# Sheet1.net
KiCad netlist of a schematic drawn in Altium Designer
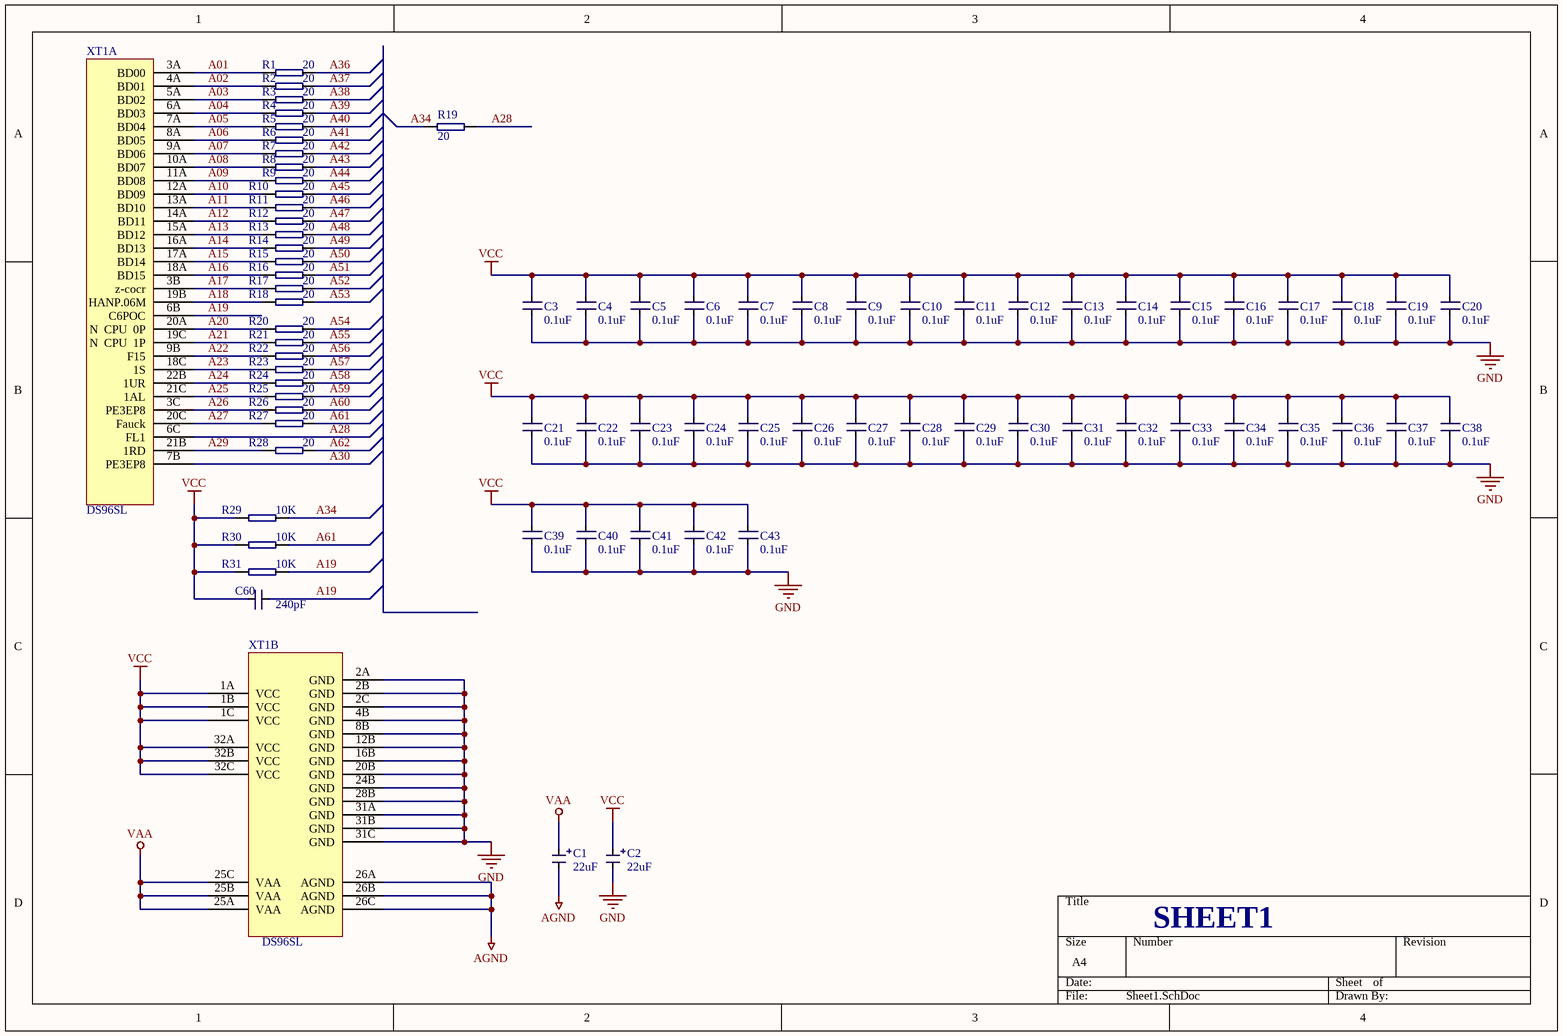
[diagram p0: Sheet1.SchDoc]

(export (version "E")
  (design (tool "Eeschema 10.0.6"))
  (components
    (comp (ref "C1")
      (value "22uF")
      (footprint "B(1812)")
      (fields (field (name "Comment") "Cap2"))
      (libsource (lib "Board2") (part "Cap2"))
    )
    (comp (ref "C2")
      (value "22uF")
      (footprint "B(1812)")
      (fields (field (name "Comment") "Cap2"))
      (libsource (lib "Board2") (part "Cap2"))
    )
    (comp (ref "C3")
      (value "0.1uF")
      (footprint "0805")
      (fields (field (name "Comment") "Cap"))
      (libsource (lib "Board2") (part "Cap"))
    )
    (comp (ref "C4")
      (value "0.1uF")
      (footprint "0805")
      (fields (field (name "Comment") "Cap"))
      (libsource (lib "Board2") (part "Cap"))
    )
    (comp (ref "C5")
      (value "0.1uF")
      (footprint "0805")
      (fields (field (name "Comment") "Cap"))
      (libsource (lib "Board2") (part "Cap"))
    )
    (comp (ref "C6")
      (value "0.1uF")
      (footprint "0805")
      (fields (field (name "Comment") "Cap"))
      (libsource (lib "Board2") (part "Cap"))
    )
    (comp (ref "C7")
      (value "0.1uF")
      (footprint "0805")
      (fields (field (name "Comment") "Cap"))
      (libsource (lib "Board2") (part "Cap"))
    )
    (comp (ref "C8")
      (value "0.1uF")
      (footprint "0805")
      (fields (field (name "Comment") "Cap"))
      (libsource (lib "Board2") (part "Cap"))
    )
    (comp (ref "C9")
      (value "0.1uF")
      (footprint "0805")
      (fields (field (name "Comment") "Cap"))
      (libsource (lib "Board2") (part "Cap"))
    )
    (comp (ref "C10")
      (value "0.1uF")
      (footprint "0805")
      (fields (field (name "Comment") "Cap"))
      (libsource (lib "Board2") (part "Cap"))
    )
    (comp (ref "C11")
      (value "0.1uF")
      (footprint "0805")
      (fields (field (name "Comment") "Cap"))
      (libsource (lib "Board2") (part "Cap"))
    )
    (comp (ref "C12")
      (value "0.1uF")
      (footprint "0805")
      (fields (field (name "Comment") "Cap"))
      (libsource (lib "Board2") (part "Cap"))
    )
    (comp (ref "C13")
      (value "0.1uF")
      (footprint "0805")
      (fields (field (name "Comment") "Cap"))
      (libsource (lib "Board2") (part "Cap"))
    )
    (comp (ref "C14")
      (value "0.1uF")
      (footprint "0805")
      (fields (field (name "Comment") "Cap"))
      (libsource (lib "Board2") (part "Cap"))
    )
    (comp (ref "C15")
      (value "0.1uF")
      (footprint "0805")
      (fields (field (name "Comment") "Cap"))
      (libsource (lib "Board2") (part "Cap"))
    )
    (comp (ref "C16")
      (value "0.1uF")
      (footprint "0805")
      (fields (field (name "Comment") "Cap"))
      (libsource (lib "Board2") (part "Cap"))
    )
    (comp (ref "C17")
      (value "0.1uF")
      (footprint "0805")
      (fields (field (name "Comment") "Cap"))
      (libsource (lib "Board2") (part "Cap"))
    )
    (comp (ref "C18")
      (value "0.1uF")
      (footprint "0805")
      (fields (field (name "Comment") "Cap"))
      (libsource (lib "Board2") (part "Cap"))
    )
    (comp (ref "C19")
      (value "0.1uF")
      (footprint "0805")
      (fields (field (name "Comment") "Cap"))
      (libsource (lib "Board2") (part "Cap"))
    )
    (comp (ref "C20")
      (value "0.1uF")
      (footprint "0805")
      (fields (field (name "Comment") "Cap"))
      (libsource (lib "Board2") (part "Cap"))
    )
    (comp (ref "C21")
      (value "0.1uF")
      (footprint "0805")
      (fields (field (name "Comment") "Cap"))
      (libsource (lib "Board2") (part "Cap"))
    )
    (comp (ref "C22")
      (value "0.1uF")
      (footprint "0805")
      (fields (field (name "Comment") "Cap"))
      (libsource (lib "Board2") (part "Cap"))
    )
    (comp (ref "C23")
      (value "0.1uF")
      (footprint "0805")
      (fields (field (name "Comment") "Cap"))
      (libsource (lib "Board2") (part "Cap"))
    )
    (comp (ref "C24")
      (value "0.1uF")
      (footprint "0805")
      (fields (field (name "Comment") "Cap"))
      (libsource (lib "Board2") (part "Cap"))
    )
    (comp (ref "C25")
      (value "0.1uF")
      (footprint "0805")
      (fields (field (name "Comment") "Cap"))
      (libsource (lib "Board2") (part "Cap"))
    )
    (comp (ref "C26")
      (value "0.1uF")
      (footprint "0805")
      (fields (field (name "Comment") "Cap"))
      (libsource (lib "Board2") (part "Cap"))
    )
    (comp (ref "C27")
      (value "0.1uF")
      (footprint "0805")
      (fields (field (name "Comment") "Cap"))
      (libsource (lib "Board2") (part "Cap"))
    )
    (comp (ref "C28")
      (value "0.1uF")
      (footprint "0805")
      (fields (field (name "Comment") "Cap"))
      (libsource (lib "Board2") (part "Cap"))
    )
    (comp (ref "C29")
      (value "0.1uF")
      (footprint "0805")
      (fields (field (name "Comment") "Cap"))
      (libsource (lib "Board2") (part "Cap"))
    )
    (comp (ref "C30")
      (value "0.1uF")
      (footprint "0805")
      (fields (field (name "Comment") "Cap"))
      (libsource (lib "Board2") (part "Cap"))
    )
    (comp (ref "C31")
      (value "0.1uF")
      (footprint "0805")
      (fields (field (name "Comment") "Cap"))
      (libsource (lib "Board2") (part "Cap"))
    )
    (comp (ref "C32")
      (value "0.1uF")
      (footprint "0805")
      (fields (field (name "Comment") "Cap"))
      (libsource (lib "Board2") (part "Cap"))
    )
    (comp (ref "C33")
      (value "0.1uF")
      (footprint "0805")
      (fields (field (name "Comment") "Cap"))
      (libsource (lib "Board2") (part "Cap"))
    )
    (comp (ref "C34")
      (value "0.1uF")
      (footprint "0805")
      (fields (field (name "Comment") "Cap"))
      (libsource (lib "Board2") (part "Cap"))
    )
    (comp (ref "C35")
      (value "0.1uF")
      (footprint "0805")
      (fields (field (name "Comment") "Cap"))
      (libsource (lib "Board2") (part "Cap"))
    )
    (comp (ref "C36")
      (value "0.1uF")
      (footprint "0805")
      (fields (field (name "Comment") "Cap"))
      (libsource (lib "Board2") (part "Cap"))
    )
    (comp (ref "C37")
      (value "0.1uF")
      (footprint "0805")
      (fields (field (name "Comment") "Cap"))
      (libsource (lib "Board2") (part "Cap"))
    )
    (comp (ref "C38")
      (value "0.1uF")
      (footprint "0805")
      (fields (field (name "Comment") "Cap"))
      (libsource (lib "Board2") (part "Cap"))
    )
    (comp (ref "C39")
      (value "0.1uF")
      (footprint "0805")
      (fields (field (name "Comment") "Cap"))
      (libsource (lib "Board2") (part "Cap"))
    )
    (comp (ref "C40")
      (value "0.1uF")
      (footprint "0805")
      (fields (field (name "Comment") "Cap"))
      (libsource (lib "Board2") (part "Cap"))
    )
    (comp (ref "C41")
      (value "0.1uF")
      (footprint "0805")
      (fields (field (name "Comment") "Cap"))
      (libsource (lib "Board2") (part "Cap"))
    )
    (comp (ref "C42")
      (value "0.1uF")
      (footprint "0805")
      (fields (field (name "Comment") "Cap"))
      (libsource (lib "Board2") (part "Cap"))
    )
    (comp (ref "C43")
      (value "0.1uF")
      (footprint "0805")
      (fields (field (name "Comment") "Cap"))
      (libsource (lib "Board2") (part "Cap"))
    )
    (comp (ref "C60")
      (value "240pF")
      (footprint "0805")
      (fields (field (name "Comment") "Cap"))
      (libsource (lib "Board2") (part "Cap"))
    )
    (comp (ref "R1")
      (value "20")
      (footprint "0805")
      (fields (field (name "Comment") "R"))
      (libsource (lib "Board2") (part "R"))
    )
    (comp (ref "R2")
      (value "20")
      (footprint "0805")
      (fields (field (name "Comment") "R"))
      (libsource (lib "Board2") (part "R"))
    )
    (comp (ref "R3")
      (value "20")
      (footprint "0805")
      (fields (field (name "Comment") "R"))
      (libsource (lib "Board2") (part "R"))
    )
    (comp (ref "R4")
      (value "20")
      (footprint "0805")
      (fields (field (name "Comment") "R"))
      (libsource (lib "Board2") (part "R"))
    )
    (comp (ref "R5")
      (value "20")
      (footprint "0805")
      (fields (field (name "Comment") "R"))
      (libsource (lib "Board2") (part "R"))
    )
    (comp (ref "R6")
      (value "20")
      (footprint "0805")
      (fields (field (name "Comment") "R"))
      (libsource (lib "Board2") (part "R"))
    )
    (comp (ref "R7")
      (value "20")
      (footprint "0805")
      (fields (field (name "Comment") "R"))
      (libsource (lib "Board2") (part "R"))
    )
    (comp (ref "R8")
      (value "20")
      (footprint "0805")
      (fields (field (name "Comment") "R"))
      (libsource (lib "Board2") (part "R"))
    )
    (comp (ref "R9")
      (value "20")
      (footprint "0805")
      (fields (field (name "Comment") "R"))
      (libsource (lib "Board2") (part "R"))
    )
    (comp (ref "R10")
      (value "20")
      (footprint "0805")
      (fields (field (name "Comment") "R"))
      (libsource (lib "Board2") (part "R"))
    )
    (comp (ref "R11")
      (value "20")
      (footprint "0805")
      (fields (field (name "Comment") "R"))
      (libsource (lib "Board2") (part "R"))
    )
    (comp (ref "R12")
      (value "20")
      (footprint "0805")
      (fields (field (name "Comment") "R"))
      (libsource (lib "Board2") (part "R"))
    )
    (comp (ref "R13")
      (value "20")
      (footprint "0805")
      (fields (field (name "Comment") "R"))
      (libsource (lib "Board2") (part "R"))
    )
    (comp (ref "R14")
      (value "20")
      (footprint "0805")
      (fields (field (name "Comment") "R"))
      (libsource (lib "Board2") (part "R"))
    )
    (comp (ref "R15")
      (value "20")
      (footprint "0805")
      (fields (field (name "Comment") "R"))
      (libsource (lib "Board2") (part "R"))
    )
    (comp (ref "R16")
      (value "20")
      (footprint "0805")
      (fields (field (name "Comment") "R"))
      (libsource (lib "Board2") (part "R"))
    )
    (comp (ref "R17")
      (value "20")
      (footprint "0805")
      (fields (field (name "Comment") "R"))
      (libsource (lib "Board2") (part "R"))
    )
    (comp (ref "R18")
      (value "20")
      (footprint "0805")
      (fields (field (name "Comment") "R"))
      (libsource (lib "Board2") (part "R"))
    )
    (comp (ref "R19")
      (value "20")
      (footprint "0805")
      (fields (field (name "Comment") "R"))
      (libsource (lib "") (part "R_1"))
    )
    (comp (ref "R20")
      (value "20")
      (footprint "0805")
      (fields (field (name "Comment") "R"))
      (libsource (lib "Board2") (part "R"))
    )
    (comp (ref "R21")
      (value "20")
      (footprint "0805")
      (fields (field (name "Comment") "R"))
      (libsource (lib "Board2") (part "R"))
    )
    (comp (ref "R22")
      (value "20")
      (footprint "0805")
      (fields (field (name "Comment") "R"))
      (libsource (lib "Board2") (part "R"))
    )
    (comp (ref "R23")
      (value "20")
      (footprint "0805")
      (fields (field (name "Comment") "R"))
      (libsource (lib "Board2") (part "R"))
    )
    (comp (ref "R24")
      (value "20")
      (footprint "0805")
      (fields (field (name "Comment") "R"))
      (libsource (lib "Board2") (part "R"))
    )
    (comp (ref "R25")
      (value "20")
      (footprint "0805")
      (fields (field (name "Comment") "R"))
      (libsource (lib "Board2") (part "R"))
    )
    (comp (ref "R26")
      (value "20")
      (footprint "0805")
      (fields (field (name "Comment") "R"))
      (libsource (lib "Board2") (part "R"))
    )
    (comp (ref "R27")
      (value "20")
      (footprint "0805")
      (fields (field (name "Comment") "R"))
      (libsource (lib "Board2") (part "R"))
    )
    (comp (ref "R28")
      (value "20")
      (footprint "0805")
      (fields (field (name "Comment") "R"))
      (libsource (lib "Board2") (part "R"))
    )
    (comp (ref "R29")
      (value "10K")
      (footprint "0805")
      (fields (field (name "Comment") "R"))
      (libsource (lib "Board2") (part "R"))
    )
    (comp (ref "R30")
      (value "10K")
      (footprint "0805")
      (fields (field (name "Comment") "R"))
      (libsource (lib "Board2") (part "R"))
    )
    (comp (ref "R31")
      (value "10K")
      (footprint "0805")
      (fields (field (name "Comment") "R"))
      (libsource (lib "Board2") (part "R"))
    )
    (comp (ref "XT1") (value "DS96SL") (footprint "DS96") (libsource (lib "Board2") (part "DS96SL")))
  )
  (nets
    (net (code "1") (name "/A01") (class "Default")
      (node (ref "R1") (pin "1") (pinfunction "1_1") (pintype "passive"))
      (node (ref "XT1") (pin "3A") (pinfunction "BD00_3A") (pintype "passive"))
    )
    (net (code "2") (name "/A02") (class "Default")
      (node (ref "R2") (pin "1") (pinfunction "1_1") (pintype "passive"))
      (node (ref "XT1") (pin "4A") (pinfunction "BD01_4A") (pintype "passive"))
    )
    (net (code "3") (name "/A03") (class "Default")
      (node (ref "R3") (pin "1") (pinfunction "1_1") (pintype "passive"))
      (node (ref "XT1") (pin "5A") (pinfunction "BD02_5A") (pintype "passive"))
    )
    (net (code "4") (name "/A04") (class "Default")
      (node (ref "R4") (pin "1") (pinfunction "1_1") (pintype "passive"))
      (node (ref "XT1") (pin "6A") (pinfunction "BD03_6A") (pintype "passive"))
    )
    (net (code "5") (name "/A05") (class "Default")
      (node (ref "R5") (pin "1") (pinfunction "1_1") (pintype "passive"))
      (node (ref "XT1") (pin "7A") (pinfunction "BD04_7A") (pintype "passive"))
    )
    (net (code "6") (name "/A06") (class "Default")
      (node (ref "R6") (pin "1") (pinfunction "1_1") (pintype "passive"))
      (node (ref "XT1") (pin "8A") (pinfunction "BD05_8A") (pintype "passive"))
    )
    (net (code "7") (name "/A07") (class "Default")
      (node (ref "R7") (pin "1") (pinfunction "1_1") (pintype "passive"))
      (node (ref "XT1") (pin "9A") (pinfunction "BD06_9A") (pintype "passive"))
    )
    (net (code "8") (name "/A08") (class "Default")
      (node (ref "R8") (pin "1") (pinfunction "1_1") (pintype "passive"))
      (node (ref "XT1") (pin "10A") (pinfunction "BD07_10A") (pintype "passive"))
    )
    (net (code "9") (name "/A09") (class "Default")
      (node (ref "R9") (pin "1") (pinfunction "1_1") (pintype "passive"))
      (node (ref "XT1") (pin "11A") (pinfunction "BD08_11A") (pintype "passive"))
    )
    (net (code "10") (name "/A10") (class "Default")
      (node (ref "R10") (pin "1") (pinfunction "1_1") (pintype "passive"))
      (node (ref "XT1") (pin "12A") (pinfunction "BD09_12A") (pintype "passive"))
    )
    (net (code "11") (name "/A11") (class "Default")
      (node (ref "R11") (pin "1") (pinfunction "1_1") (pintype "passive"))
      (node (ref "XT1") (pin "13A") (pinfunction "BD10_13A") (pintype "passive"))
    )
    (net (code "12") (name "/A12") (class "Default")
      (node (ref "R12") (pin "1") (pinfunction "1_1") (pintype "passive"))
      (node (ref "XT1") (pin "14A") (pinfunction "BD11_14A") (pintype "passive"))
    )
    (net (code "13") (name "/A13") (class "Default")
      (node (ref "R13") (pin "1") (pinfunction "1_1") (pintype "passive"))
      (node (ref "XT1") (pin "15A") (pinfunction "BD12_15A") (pintype "passive"))
    )
    (net (code "14") (name "/A14") (class "Default")
      (node (ref "R14") (pin "1") (pinfunction "1_1") (pintype "passive"))
      (node (ref "XT1") (pin "16A") (pinfunction "BD13_16A") (pintype "passive"))
    )
    (net (code "15") (name "/A15") (class "Default")
      (node (ref "R15") (pin "1") (pinfunction "1_1") (pintype "passive"))
      (node (ref "XT1") (pin "17A") (pinfunction "BD14_17A") (pintype "passive"))
    )
    (net (code "16") (name "/A16") (class "Default")
      (node (ref "R16") (pin "1") (pinfunction "1_1") (pintype "passive"))
      (node (ref "XT1") (pin "18A") (pinfunction "BD15_18A") (pintype "passive"))
    )
    (net (code "17") (name "/A17") (class "Default")
      (node (ref "R17") (pin "1") (pinfunction "1_1") (pintype "passive"))
      (node (ref "XT1") (pin "3B") (pinfunction "z-cocr_3B") (pintype "passive"))
    )
    (net (code "18") (name "/A18") (class "Default")
      (node (ref "R18") (pin "1") (pinfunction "1_1") (pintype "passive"))
      (node (ref "XT1") (pin "19B") (pinfunction "HANP.06M_19B") (pintype "passive"))
    )
    (net (code "19") (name "/A19") (class "Default")
      (node (ref "C60") (pin "2") (pinfunction "0_2") (pintype "passive"))
      (node (ref "R31") (pin "2") (pinfunction "0_2") (pintype "passive"))
      (node (ref "XT1") (pin "6B") (pinfunction "C6POC_6B") (pintype "passive"))
    )
    (net (code "20") (name "/A20") (class "Default")
      (node (ref "R20") (pin "1") (pinfunction "1_1") (pintype "passive"))
      (node (ref "XT1") (pin "20A") (pinfunction "N__CPU__0P_20A") (pintype "passive"))
    )
    (net (code "21") (name "/A21") (class "Default")
      (node (ref "R21") (pin "1") (pinfunction "1_1") (pintype "passive"))
      (node (ref "XT1") (pin "19C") (pinfunction "N__CPU__1P_19C") (pintype "passive"))
    )
    (net (code "22") (name "/A22") (class "Default")
      (node (ref "R22") (pin "1") (pinfunction "1_1") (pintype "passive"))
      (node (ref "XT1") (pin "9B") (pinfunction "F15_9B") (pintype "passive"))
    )
    (net (code "23") (name "/A23") (class "Default")
      (node (ref "R23") (pin "1") (pinfunction "1_1") (pintype "passive"))
      (node (ref "XT1") (pin "18C") (pinfunction "1S_18C") (pintype "passive"))
    )
    (net (code "24") (name "/A24") (class "Default")
      (node (ref "R24") (pin "1") (pinfunction "1_1") (pintype "passive"))
      (node (ref "XT1") (pin "22B") (pinfunction "1UR_22B") (pintype "passive"))
    )
    (net (code "25") (name "/A25") (class "Default")
      (node (ref "R25") (pin "1") (pinfunction "1_1") (pintype "passive"))
      (node (ref "XT1") (pin "21C") (pinfunction "1AL_21C") (pintype "passive"))
    )
    (net (code "26") (name "/A26") (class "Default")
      (node (ref "R26") (pin "1") (pinfunction "1_1") (pintype "passive"))
      (node (ref "XT1") (pin "3C") (pinfunction "PE3EP8_3C") (pintype "passive"))
    )
    (net (code "27") (name "/A27") (class "Default")
      (node (ref "R27") (pin "1") (pinfunction "1_1") (pintype "passive"))
      (node (ref "XT1") (pin "20C") (pinfunction "Fauck_20C") (pintype "passive"))
    )
    (net (code "28") (name "/A28") (class "Default")
      (node (ref "R19") (pin "1") (pinfunction "1_1") (pintype "passive"))
      (node (ref "XT1") (pin "6C") (pinfunction "FL1_6C") (pintype "passive"))
    )
    (net (code "29") (name "/A29") (class "Default")
      (node (ref "R28") (pin "1") (pinfunction "1_1") (pintype "passive"))
      (node (ref "XT1") (pin "21B") (pinfunction "1RD_21B") (pintype "passive"))
    )
    (net (code "30") (name "/A30") (class "Default")
      (node (ref "XT1") (pin "7B") (pinfunction "PE3EP8_7B") (pintype "passive"))
    )
    (net (code "31") (name "/A34") (class "Default")
      (node (ref "R19") (pin "2") (pinfunction "0_2") (pintype "passive"))
      (node (ref "R29") (pin "2") (pinfunction "0_2") (pintype "passive"))
    )
    (net (code "32") (name "/A36") (class "Default")
      (node (ref "R1") (pin "2") (pinfunction "0_2") (pintype "passive"))
    )
    (net (code "33") (name "/A37") (class "Default")
      (node (ref "R2") (pin "2") (pinfunction "0_2") (pintype "passive"))
    )
    (net (code "34") (name "/A38") (class "Default")
      (node (ref "R3") (pin "2") (pinfunction "0_2") (pintype "passive"))
    )
    (net (code "35") (name "/A39") (class "Default")
      (node (ref "R4") (pin "2") (pinfunction "0_2") (pintype "passive"))
    )
    (net (code "36") (name "/A40") (class "Default")
      (node (ref "R5") (pin "2") (pinfunction "0_2") (pintype "passive"))
    )
    (net (code "37") (name "/A41") (class "Default")
      (node (ref "R6") (pin "2") (pinfunction "0_2") (pintype "passive"))
    )
    (net (code "38") (name "/A42") (class "Default")
      (node (ref "R7") (pin "2") (pinfunction "0_2") (pintype "passive"))
    )
    (net (code "39") (name "/A43") (class "Default")
      (node (ref "R8") (pin "2") (pinfunction "0_2") (pintype "passive"))
    )
    (net (code "40") (name "/A44") (class "Default")
      (node (ref "R9") (pin "2") (pinfunction "0_2") (pintype "passive"))
    )
    (net (code "41") (name "/A45") (class "Default")
      (node (ref "R10") (pin "2") (pinfunction "0_2") (pintype "passive"))
    )
    (net (code "42") (name "/A46") (class "Default")
      (node (ref "R11") (pin "2") (pinfunction "0_2") (pintype "passive"))
    )
    (net (code "43") (name "/A47") (class "Default")
      (node (ref "R12") (pin "2") (pinfunction "0_2") (pintype "passive"))
    )
    (net (code "44") (name "/A48") (class "Default")
      (node (ref "R13") (pin "2") (pinfunction "0_2") (pintype "passive"))
    )
    (net (code "45") (name "/A49") (class "Default")
      (node (ref "R14") (pin "2") (pinfunction "0_2") (pintype "passive"))
    )
    (net (code "46") (name "/A50") (class "Default")
      (node (ref "R15") (pin "2") (pinfunction "0_2") (pintype "passive"))
    )
    (net (code "47") (name "/A51") (class "Default")
      (node (ref "R16") (pin "2") (pinfunction "0_2") (pintype "passive"))
    )
    (net (code "48") (name "/A52") (class "Default")
      (node (ref "R17") (pin "2") (pinfunction "0_2") (pintype "passive"))
    )
    (net (code "49") (name "/A53") (class "Default")
      (node (ref "R18") (pin "2") (pinfunction "0_2") (pintype "passive"))
    )
    (net (code "50") (name "/A54") (class "Default")
      (node (ref "R20") (pin "2") (pinfunction "0_2") (pintype "passive"))
    )
    (net (code "51") (name "/A55") (class "Default")
      (node (ref "R21") (pin "2") (pinfunction "0_2") (pintype "passive"))
    )
    (net (code "52") (name "/A56") (class "Default")
      (node (ref "R22") (pin "2") (pinfunction "0_2") (pintype "passive"))
    )
    (net (code "53") (name "/A57") (class "Default")
      (node (ref "R23") (pin "2") (pinfunction "0_2") (pintype "passive"))
    )
    (net (code "54") (name "/A58") (class "Default")
      (node (ref "R24") (pin "2") (pinfunction "0_2") (pintype "passive"))
    )
    (net (code "55") (name "/A59") (class "Default")
      (node (ref "R25") (pin "2") (pinfunction "0_2") (pintype "passive"))
    )
    (net (code "56") (name "/A60") (class "Default")
      (node (ref "R26") (pin "2") (pinfunction "0_2") (pintype "passive"))
    )
    (net (code "57") (name "/A61") (class "Default")
      (node (ref "R27") (pin "2") (pinfunction "0_2") (pintype "passive"))
      (node (ref "R30") (pin "2") (pinfunction "0_2") (pintype "passive"))
    )
    (net (code "58") (name "/A62") (class "Default")
      (node (ref "R28") (pin "2") (pinfunction "0_2") (pintype "passive"))
    )
    (net (code "59") (name "AGND") (class "Default")
      (node (ref "C1") (pin "2") (pinfunction "0_2") (pintype "passive"))
      (node (ref "XT1") (pin "26A") (pinfunction "AGND_26A") (pintype "passive"))
      (node (ref "XT1") (pin "26B") (pinfunction "AGND_26B") (pintype "passive"))
      (node (ref "XT1") (pin "26C") (pinfunction "AGND_26C") (pintype "passive"))
    )
    (net (code "60") (name "GND") (class "Default")
      (node (ref "C10") (pin "1") (pinfunction "1_1") (pintype "passive"))
      (node (ref "C11") (pin "1") (pinfunction "1_1") (pintype "passive"))
      (node (ref "C12") (pin "1") (pinfunction "1_1") (pintype "passive"))
      (node (ref "C13") (pin "1") (pinfunction "1_1") (pintype "passive"))
      (node (ref "C14") (pin "1") (pinfunction "1_1") (pintype "passive"))
      (node (ref "C15") (pin "1") (pinfunction "1_1") (pintype "passive"))
      (node (ref "C16") (pin "1") (pinfunction "1_1") (pintype "passive"))
      (node (ref "C17") (pin "1") (pinfunction "1_1") (pintype "passive"))
      (node (ref "C18") (pin "1") (pinfunction "1_1") (pintype "passive"))
      (node (ref "C19") (pin "1") (pinfunction "1_1") (pintype "passive"))
      (node (ref "C2") (pin "2") (pinfunction "0_2") (pintype "passive"))
      (node (ref "C20") (pin "1") (pinfunction "1_1") (pintype "passive"))
      (node (ref "C21") (pin "1") (pinfunction "1_1") (pintype "passive"))
      (node (ref "C22") (pin "1") (pinfunction "1_1") (pintype "passive"))
      (node (ref "C23") (pin "1") (pinfunction "1_1") (pintype "passive"))
      (node (ref "C24") (pin "1") (pinfunction "1_1") (pintype "passive"))
      (node (ref "C25") (pin "1") (pinfunction "1_1") (pintype "passive"))
      (node (ref "C26") (pin "1") (pinfunction "1_1") (pintype "passive"))
      (node (ref "C27") (pin "1") (pinfunction "1_1") (pintype "passive"))
      (node (ref "C28") (pin "1") (pinfunction "1_1") (pintype "passive"))
      (node (ref "C29") (pin "1") (pinfunction "1_1") (pintype "passive"))
      (node (ref "C3") (pin "1") (pinfunction "1_1") (pintype "passive"))
      (node (ref "C30") (pin "1") (pinfunction "1_1") (pintype "passive"))
      (node (ref "C31") (pin "1") (pinfunction "1_1") (pintype "passive"))
      (node (ref "C32") (pin "1") (pinfunction "1_1") (pintype "passive"))
      (node (ref "C33") (pin "1") (pinfunction "1_1") (pintype "passive"))
      (node (ref "C34") (pin "1") (pinfunction "1_1") (pintype "passive"))
      (node (ref "C35") (pin "1") (pinfunction "1_1") (pintype "passive"))
      (node (ref "C36") (pin "1") (pinfunction "1_1") (pintype "passive"))
      (node (ref "C37") (pin "1") (pinfunction "1_1") (pintype "passive"))
      (node (ref "C38") (pin "1") (pinfunction "1_1") (pintype "passive"))
      (node (ref "C39") (pin "1") (pinfunction "1_1") (pintype "passive"))
      (node (ref "C4") (pin "1") (pinfunction "1_1") (pintype "passive"))
      (node (ref "C40") (pin "1") (pinfunction "1_1") (pintype "passive"))
      (node (ref "C41") (pin "1") (pinfunction "1_1") (pintype "passive"))
      (node (ref "C42") (pin "1") (pinfunction "1_1") (pintype "passive"))
      (node (ref "C43") (pin "1") (pinfunction "1_1") (pintype "passive"))
      (node (ref "C5") (pin "1") (pinfunction "1_1") (pintype "passive"))
      (node (ref "C6") (pin "1") (pinfunction "1_1") (pintype "passive"))
      (node (ref "C7") (pin "1") (pinfunction "1_1") (pintype "passive"))
      (node (ref "C8") (pin "1") (pinfunction "1_1") (pintype "passive"))
      (node (ref "C9") (pin "1") (pinfunction "1_1") (pintype "passive"))
      (node (ref "XT1") (pin "12B") (pinfunction "GND_12B") (pintype "passive"))
      (node (ref "XT1") (pin "16B") (pinfunction "GND_16B") (pintype "passive"))
      (node (ref "XT1") (pin "20B") (pinfunction "GND_20B") (pintype "passive"))
      (node (ref "XT1") (pin "24B") (pinfunction "GND_24B") (pintype "passive"))
      (node (ref "XT1") (pin "28B") (pinfunction "GND_28B") (pintype "passive"))
      (node (ref "XT1") (pin "2A") (pinfunction "GND_2A") (pintype "passive"))
      (node (ref "XT1") (pin "2B") (pinfunction "GND_2B") (pintype "passive"))
      (node (ref "XT1") (pin "2C") (pinfunction "GND_2C") (pintype "passive"))
      (node (ref "XT1") (pin "31A") (pinfunction "GND_31A") (pintype "passive"))
      (node (ref "XT1") (pin "31B") (pinfunction "GND_31B") (pintype "passive"))
      (node (ref "XT1") (pin "31C") (pinfunction "GND_31C") (pintype "passive"))
      (node (ref "XT1") (pin "4B") (pinfunction "GND_4B") (pintype "passive"))
      (node (ref "XT1") (pin "8B") (pinfunction "GND_8B") (pintype "passive"))
    )
    (net (code "61") (name "VAA") (class "Default")
      (node (ref "C1") (pin "1") (pinfunction "1_1") (pintype "passive"))
      (node (ref "XT1") (pin "25A") (pinfunction "VAA_25A") (pintype "passive"))
      (node (ref "XT1") (pin "25B") (pinfunction "VAA_25B") (pintype "passive"))
      (node (ref "XT1") (pin "25C") (pinfunction "VAA_25C") (pintype "passive"))
    )
    (net (code "62") (name "VCC") (class "Default")
      (node (ref "C10") (pin "2") (pinfunction "0_2") (pintype "passive"))
      (node (ref "C11") (pin "2") (pinfunction "0_2") (pintype "passive"))
      (node (ref "C12") (pin "2") (pinfunction "0_2") (pintype "passive"))
      (node (ref "C13") (pin "2") (pinfunction "0_2") (pintype "passive"))
      (node (ref "C14") (pin "2") (pinfunction "0_2") (pintype "passive"))
      (node (ref "C15") (pin "2") (pinfunction "0_2") (pintype "passive"))
      (node (ref "C16") (pin "2") (pinfunction "0_2") (pintype "passive"))
      (node (ref "C17") (pin "2") (pinfunction "0_2") (pintype "passive"))
      (node (ref "C18") (pin "2") (pinfunction "0_2") (pintype "passive"))
      (node (ref "C19") (pin "2") (pinfunction "0_2") (pintype "passive"))
      (node (ref "C2") (pin "1") (pinfunction "1_1") (pintype "passive"))
      (node (ref "C20") (pin "2") (pinfunction "0_2") (pintype "passive"))
      (node (ref "C21") (pin "2") (pinfunction "0_2") (pintype "passive"))
      (node (ref "C22") (pin "2") (pinfunction "0_2") (pintype "passive"))
      (node (ref "C23") (pin "2") (pinfunction "0_2") (pintype "passive"))
      (node (ref "C24") (pin "2") (pinfunction "0_2") (pintype "passive"))
      (node (ref "C25") (pin "2") (pinfunction "0_2") (pintype "passive"))
      (node (ref "C26") (pin "2") (pinfunction "0_2") (pintype "passive"))
      (node (ref "C27") (pin "2") (pinfunction "0_2") (pintype "passive"))
      (node (ref "C28") (pin "2") (pinfunction "0_2") (pintype "passive"))
      (node (ref "C29") (pin "2") (pinfunction "0_2") (pintype "passive"))
      (node (ref "C3") (pin "2") (pinfunction "0_2") (pintype "passive"))
      (node (ref "C30") (pin "2") (pinfunction "0_2") (pintype "passive"))
      (node (ref "C31") (pin "2") (pinfunction "0_2") (pintype "passive"))
      (node (ref "C32") (pin "2") (pinfunction "0_2") (pintype "passive"))
      (node (ref "C33") (pin "2") (pinfunction "0_2") (pintype "passive"))
      (node (ref "C34") (pin "2") (pinfunction "0_2") (pintype "passive"))
      (node (ref "C35") (pin "2") (pinfunction "0_2") (pintype "passive"))
      (node (ref "C36") (pin "2") (pinfunction "0_2") (pintype "passive"))
      (node (ref "C37") (pin "2") (pinfunction "0_2") (pintype "passive"))
      (node (ref "C38") (pin "2") (pinfunction "0_2") (pintype "passive"))
      (node (ref "C39") (pin "2") (pinfunction "0_2") (pintype "passive"))
      (node (ref "C4") (pin "2") (pinfunction "0_2") (pintype "passive"))
      (node (ref "C40") (pin "2") (pinfunction "0_2") (pintype "passive"))
      (node (ref "C41") (pin "2") (pinfunction "0_2") (pintype "passive"))
      (node (ref "C42") (pin "2") (pinfunction "0_2") (pintype "passive"))
      (node (ref "C43") (pin "2") (pinfunction "0_2") (pintype "passive"))
      (node (ref "C5") (pin "2") (pinfunction "0_2") (pintype "passive"))
      (node (ref "C6") (pin "2") (pinfunction "0_2") (pintype "passive"))
      (node (ref "C60") (pin "1") (pinfunction "1_1") (pintype "passive"))
      (node (ref "C7") (pin "2") (pinfunction "0_2") (pintype "passive"))
      (node (ref "C8") (pin "2") (pinfunction "0_2") (pintype "passive"))
      (node (ref "C9") (pin "2") (pinfunction "0_2") (pintype "passive"))
      (node (ref "R29") (pin "1") (pinfunction "1_1") (pintype "passive"))
      (node (ref "R30") (pin "1") (pinfunction "1_1") (pintype "passive"))
      (node (ref "R31") (pin "1") (pinfunction "1_1") (pintype "passive"))
      (node (ref "XT1") (pin "1A") (pinfunction "VCC_1A") (pintype "passive"))
      (node (ref "XT1") (pin "1B") (pinfunction "VCC_1B") (pintype "passive"))
      (node (ref "XT1") (pin "1C") (pinfunction "VCC_1C") (pintype "passive"))
      (node (ref "XT1") (pin "32A") (pinfunction "VCC_32A") (pintype "passive"))
      (node (ref "XT1") (pin "32B") (pinfunction "VCC_32B") (pintype "passive"))
      (node (ref "XT1") (pin "32C") (pinfunction "VCC_32C") (pintype "passive"))
    )
  )
)
